# psb_schematic.net
KiCad netlist of a schematic drawn in EAGLE
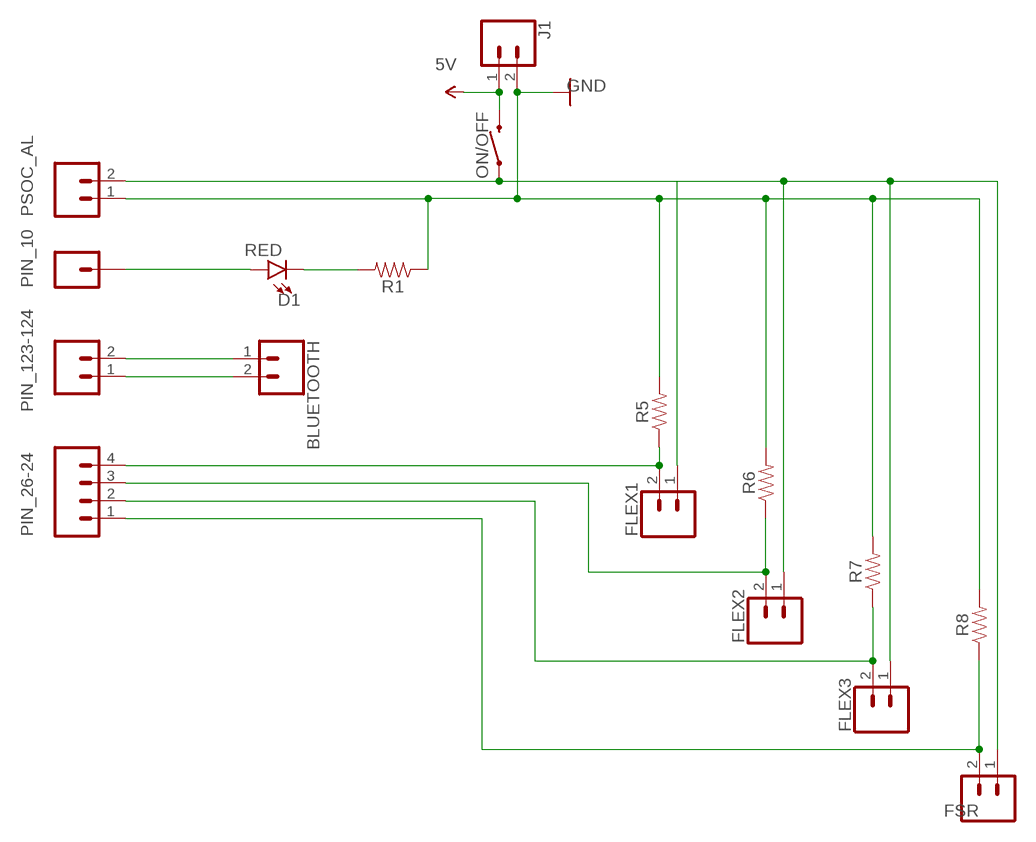
[diagram p0: schematic, sheet 1]

(export (version "E")
  (design (tool "Eeschema 10.0.6"))
  (components
    (comp (ref "BLUETOOTH")
      (value "CONN_02")
      (footprint "eagle-import:1X02")
      (libsource (lib "eagle-import") (part "CONN_02"))
    )
    (comp (ref "D1")
      (value "RED")
      (footprint "eagle-import:LED-0603")
      (libsource (lib "eagle-import") (part "LED-RED0603"))
    )
    (comp (ref "FLEX1")
      (value "CONN_02")
      (footprint "eagle-import:1X02")
      (libsource (lib "eagle-import") (part "CONN_02"))
    )
    (comp (ref "FLEX2")
      (value "CONN_02")
      (footprint "eagle-import:1X02")
      (libsource (lib "eagle-import") (part "CONN_02"))
    )
    (comp (ref "FLEX3")
      (value "CONN_02")
      (footprint "eagle-import:1X02")
      (libsource (lib "eagle-import") (part "CONN_02"))
    )
    (comp (ref "FSR")
      (value "CONN_02")
      (footprint "eagle-import:1X02")
      (libsource (lib "eagle-import") (part "CONN_02"))
    )
    (comp (ref "J1")
      (value "CONN_02")
      (footprint "eagle-import:1X02")
      (libsource (lib "eagle-import") (part "CONN_02"))
    )
    (comp (ref "ON/OFF")
      (value "MOMENTARY-SWITCH-SPST-SMD-6.0X3.5MM")
      (footprint "eagle-import:TACTILE_SWITCH_SMD_6.0X3.5MM")
      (libsource (lib "eagle-import") (part "MOMENTARY-SWITCH-SPST-SMD-6.0X3.5MM"))
    )
    (comp (ref "PIN_10")
      (value "CONN_01")
      (footprint "eagle-import:1X01")
      (libsource (lib "eagle-import") (part "CONN_01"))
    )
    (comp (ref "PIN_26-24")
      (value "CONN_04")
      (footprint "eagle-import:1X04")
      (libsource (lib "eagle-import") (part "CONN_04"))
    )
    (comp (ref "PIN_123-124")
      (value "CONN_02")
      (footprint "eagle-import:1X02")
      (libsource (lib "eagle-import") (part "CONN_02"))
    )
    (comp (ref "PSOC_AL")
      (value "CONN_02")
      (footprint "eagle-import:1X02")
      (libsource (lib "eagle-import") (part "CONN_02"))
    )
    (comp (ref "R1")
      (value "RESISTORAXIAL-0.3")
      (footprint "eagle-import:AXIAL-0.3")
      (libsource (lib "eagle-import") (part "RESISTORAXIAL-0.3"))
    )
    (comp (ref "R5")
      (value "RESISTORAXIAL-0.3")
      (footprint "eagle-import:AXIAL-0.3")
      (libsource (lib "eagle-import") (part "RESISTORAXIAL-0.3"))
    )
    (comp (ref "R6")
      (value "RESISTORAXIAL-0.3")
      (footprint "eagle-import:AXIAL-0.3")
      (libsource (lib "eagle-import") (part "RESISTORAXIAL-0.3"))
    )
    (comp (ref "R7")
      (value "RESISTORAXIAL-0.3")
      (footprint "eagle-import:AXIAL-0.3")
      (libsource (lib "eagle-import") (part "RESISTORAXIAL-0.3"))
    )
    (comp (ref "R8")
      (value "RESISTORAXIAL-0.3")
      (footprint "eagle-import:AXIAL-0.3")
      (libsource (lib "eagle-import") (part "RESISTORAXIAL-0.3"))
    )
  )
  (nets
    (net (code "1") (name "5V") (class "Default")
      (node (ref "J1") (pin "1") (pinfunction "1_1") (pintype "passive"))
      (node (ref "ON/OFF") (pin "2") (pinfunction "2_2") (pintype "passive"))
    )
    (net (code "2") (name "GND") (class "Default")
      (node (ref "J1") (pin "2") (pinfunction "2_2") (pintype "passive"))
      (node (ref "PSOC_AL") (pin "1") (pinfunction "1_1") (pintype "passive"))
      (node (ref "R1") (pin "P$1") (pinfunction "1_P$1") (pintype "passive"))
      (node (ref "R5") (pin "P$2") (pinfunction "2_P$2") (pintype "passive"))
      (node (ref "R6") (pin "P$2") (pinfunction "2_P$2") (pintype "passive"))
      (node (ref "R7") (pin "P$2") (pinfunction "2_P$2") (pintype "passive"))
      (node (ref "R8") (pin "P$2") (pinfunction "2_P$2") (pintype "passive"))
    )
    (net (code "3") (name "Net-(BLUETOOTH-Pad1)") (class "Default")
      (node (ref "BLUETOOTH") (pin "1") (pinfunction "1_1") (pintype "passive"))
      (node (ref "PIN_123-124") (pin "2") (pinfunction "2_2") (pintype "passive"))
    )
    (net (code "4") (name "Net-(BLUETOOTH-Pad2)") (class "Default")
      (node (ref "BLUETOOTH") (pin "2") (pinfunction "2_2") (pintype "passive"))
      (node (ref "PIN_123-124") (pin "1") (pinfunction "1_1") (pintype "passive"))
    )
    (net (code "5") (name "Net-(D1-PadA)") (class "Default")
      (node (ref "D1") (pin "A") (pinfunction "A_A") (pintype "passive"))
      (node (ref "PIN_10") (pin "1") (pinfunction "1_1") (pintype "passive"))
    )
    (net (code "6") (name "Net-(FLEX1-Pad1)") (class "Default")
      (node (ref "FLEX1") (pin "1") (pinfunction "1_1") (pintype "passive"))
      (node (ref "FLEX2") (pin "1") (pinfunction "1_1") (pintype "passive"))
      (node (ref "FLEX3") (pin "1") (pinfunction "1_1") (pintype "passive"))
      (node (ref "FSR") (pin "1") (pinfunction "1_1") (pintype "passive"))
      (node (ref "ON/OFF") (pin "1") (pinfunction "1_1") (pintype "passive"))
      (node (ref "PSOC_AL") (pin "2") (pinfunction "2_2") (pintype "passive"))
    )
    (net (code "7") (name "Net-(R1-2)") (class "Default")
      (node (ref "D1") (pin "C") (pinfunction "C_C") (pintype "passive"))
      (node (ref "R1") (pin "P$2") (pinfunction "2_P$2") (pintype "passive"))
    )
    (net (code "8") (name "Net-(R5-1)") (class "Default")
      (node (ref "FLEX1") (pin "2") (pinfunction "2_2") (pintype "passive"))
      (node (ref "PIN_26-24") (pin "4") (pinfunction "4_4") (pintype "passive"))
      (node (ref "R5") (pin "P$1") (pinfunction "1_P$1") (pintype "passive"))
    )
    (net (code "9") (name "Net-(R6-1)") (class "Default")
      (node (ref "FLEX2") (pin "2") (pinfunction "2_2") (pintype "passive"))
      (node (ref "PIN_26-24") (pin "3") (pinfunction "3_3") (pintype "passive"))
      (node (ref "R6") (pin "P$1") (pinfunction "1_P$1") (pintype "passive"))
    )
    (net (code "10") (name "Net-(R7-1)") (class "Default")
      (node (ref "FLEX3") (pin "2") (pinfunction "2_2") (pintype "passive"))
      (node (ref "PIN_26-24") (pin "2") (pinfunction "2_2") (pintype "passive"))
      (node (ref "R7") (pin "P$1") (pinfunction "1_P$1") (pintype "passive"))
    )
    (net (code "11") (name "Net-(R8-1)") (class "Default")
      (node (ref "FSR") (pin "2") (pinfunction "2_2") (pintype "passive"))
      (node (ref "PIN_26-24") (pin "1") (pinfunction "1_1") (pintype "passive"))
      (node (ref "R8") (pin "P$1") (pinfunction "1_P$1") (pintype "passive"))
    )
  )
)
